# 6_BMS_OK_Fans.net
KiCad netlist of a schematic drawn in Altium Designer
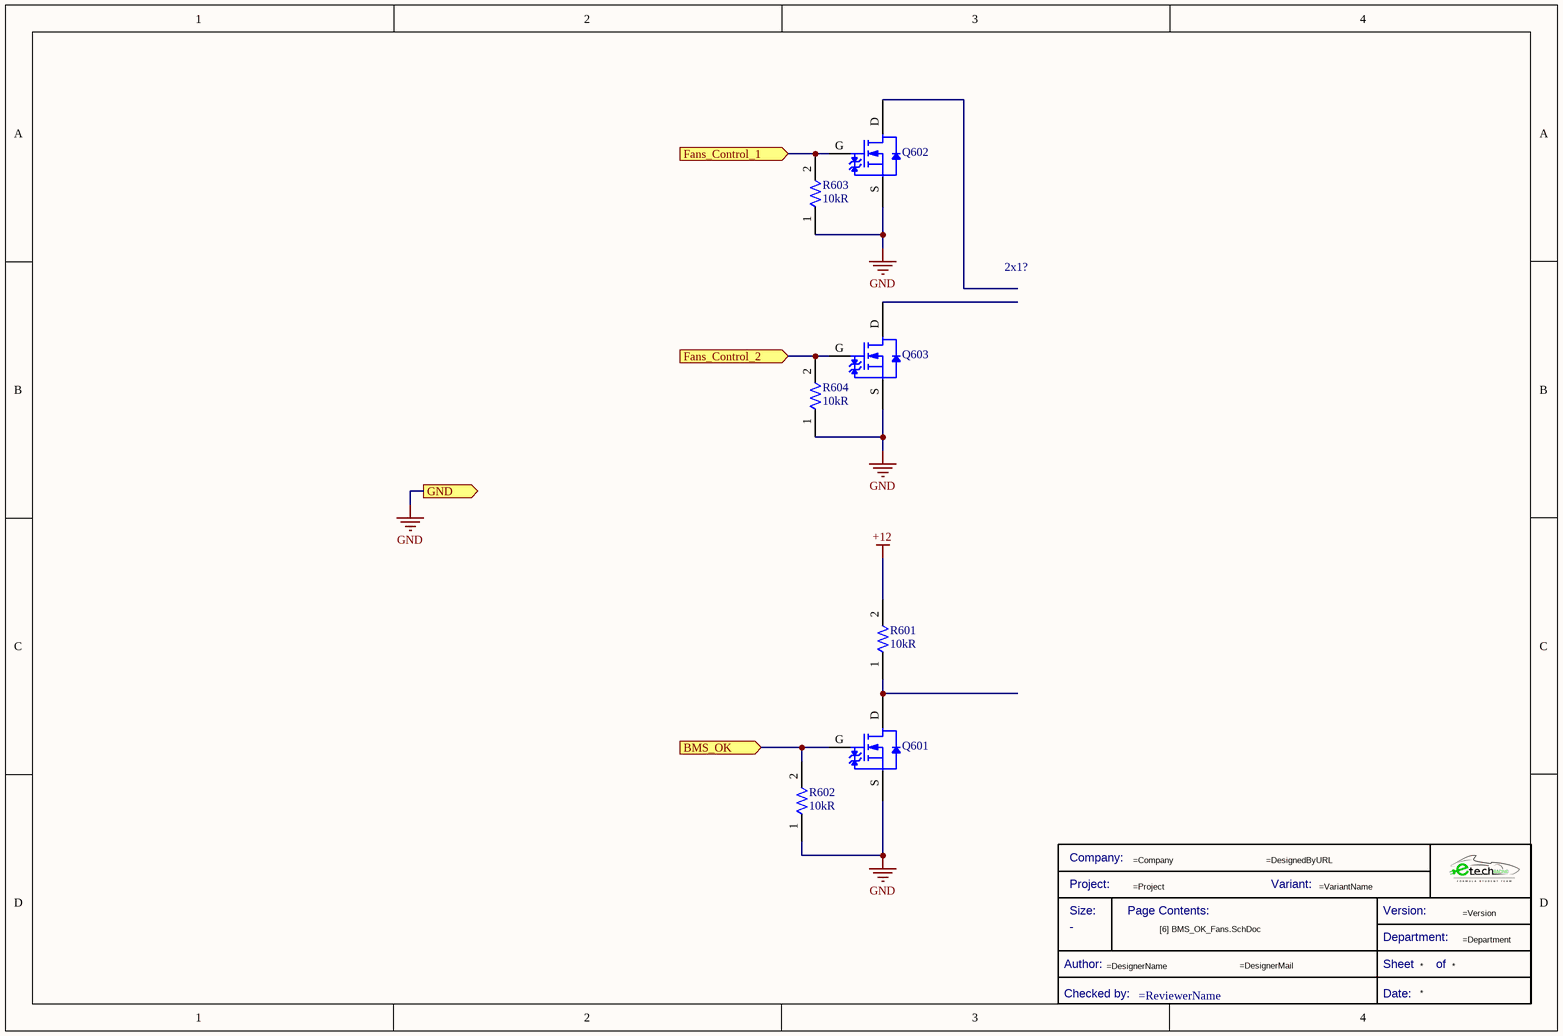
[diagram p0: [6] BMS_OK_Fans.SchDoc]

(export (version "E")
  (design (tool "Eeschema 10.0.6"))
  (components
    (comp (ref "*")
      (value "Title Block_template")
      (description "Standard Title Block")
      (fields (field (name "SIZE") "-"))
      (libsource (lib "e-Tech_Racing") (part "Title Block_template"))
    )
    (comp (ref "Q601")
      (value "CPH3455-TL-H")
      (footprint "TRT-NCH-3/35-CPH")
      (description "CPH3455-TL-H N-channel MOSFET Transistor; 3 A; 35 V; 3-Pin CPH")
      (fields (field (name "MANUFACTURER") "ON Semiconductor"))
      (libsource (lib "Semiconductor") (part "TRT-NCH-3/35-CPH"))
    )
    (comp (ref "Q602")
      (value "CPH3455-TL-H")
      (footprint "TRT-NCH-3/35-CPH")
      (description "CPH3455-TL-H N-channel MOSFET Transistor; 3 A; 35 V; 3-Pin CPH")
      (fields (field (name "MANUFACTURER") "ON Semiconductor"))
      (libsource (lib "Semiconductor") (part "TRT-NCH-3/35-CPH"))
    )
    (comp (ref "Q603")
      (value "CPH3455-TL-H")
      (footprint "TRT-NCH-3/35-CPH")
      (description "CPH3455-TL-H N-channel MOSFET Transistor; 3 A; 35 V; 3-Pin CPH")
      (fields (field (name "MANUFACTURER") "ON Semiconductor"))
      (libsource (lib "Semiconductor") (part "TRT-NCH-3/35-CPH"))
    )
    (comp (ref "R601")
      (value "CR0805-JW-103ELF")
      (footprint "R0805FTK")
      (fields (field (name "TOLERANCE") "5%") (field (name "RESISTANCE") "10kR"))
      (libsource (lib "Passives") (part "R10k-0805FTK"))
    )
    (comp (ref "R602")
      (value "CR0805-JW-103ELF")
      (footprint "R0805FTK")
      (fields (field (name "TOLERANCE") "5%") (field (name "RESISTANCE") "10kR"))
      (libsource (lib "Passives") (part "R10k-0805FTK"))
    )
    (comp (ref "R603")
      (value "CR0805-JW-103ELF")
      (footprint "R0805FTK")
      (fields (field (name "TOLERANCE") "5%") (field (name "RESISTANCE") "10kR"))
      (libsource (lib "Passives") (part "R10k-0805FTK"))
    )
    (comp (ref "R604")
      (value "CR0805-JW-103ELF")
      (footprint "R0805FTK")
      (fields (field (name "TOLERANCE") "5%") (field (name "RESISTANCE") "10kR"))
      (libsource (lib "Passives") (part "R10k-0805FTK"))
    )
  )
  (nets
    (net (code "1") (name "+12") (class "Default")
      (node (ref "R601") (pin "2") (pinfunction "2_2") (pintype "passive"))
    )
    (net (code "2") (name "/BMS_OK") (class "Default")
      (node (ref "Q601") (pin "G") (pinfunction "G_G") (pintype "passive"))
      (node (ref "R602") (pin "2") (pinfunction "2_2") (pintype "passive"))
    )
    (net (code "3") (name "/Fans_Control_1") (class "Default")
      (node (ref "Q602") (pin "G") (pinfunction "G_G") (pintype "passive"))
      (node (ref "R603") (pin "2") (pinfunction "2_2") (pintype "passive"))
    )
    (net (code "4") (name "/Fans_Control_2") (class "Default")
      (node (ref "Q603") (pin "G") (pinfunction "G_G") (pintype "passive"))
      (node (ref "R604") (pin "2") (pinfunction "2_2") (pintype "passive"))
    )
    (net (code "5") (name "GND") (class "Default")
      (node (ref "Q601") (pin "S") (pinfunction "S_S") (pintype "passive"))
      (node (ref "Q602") (pin "S") (pinfunction "S_S") (pintype "passive"))
      (node (ref "Q603") (pin "S") (pinfunction "S_S") (pintype "passive"))
      (node (ref "R602") (pin "1") (pinfunction "1_1") (pintype "passive"))
      (node (ref "R603") (pin "1") (pinfunction "1_1") (pintype "passive"))
      (node (ref "R604") (pin "1") (pinfunction "1_1") (pintype "passive"))
    )
    (net (code "6") (name "Net-(Q601-PadD)") (class "Default")
      (node (ref "Q601") (pin "D") (pinfunction "D_D") (pintype "passive"))
      (node (ref "R601") (pin "1") (pinfunction "1_1") (pintype "passive"))
    )
    (net (code "7") (name "unconnected-(Q602-PadD)") (class "Default")
      (node (ref "Q602") (pin "D") (pinfunction "D_D") (pintype "passive"))
    )
    (net (code "8") (name "unconnected-(Q603-PadD)") (class "Default")
      (node (ref "Q603") (pin "D") (pinfunction "D_D") (pintype "passive"))
    )
  )
)
